# BGHESP32_Base_v1_1.net
KiCad netlist of a schematic drawn in EAGLE
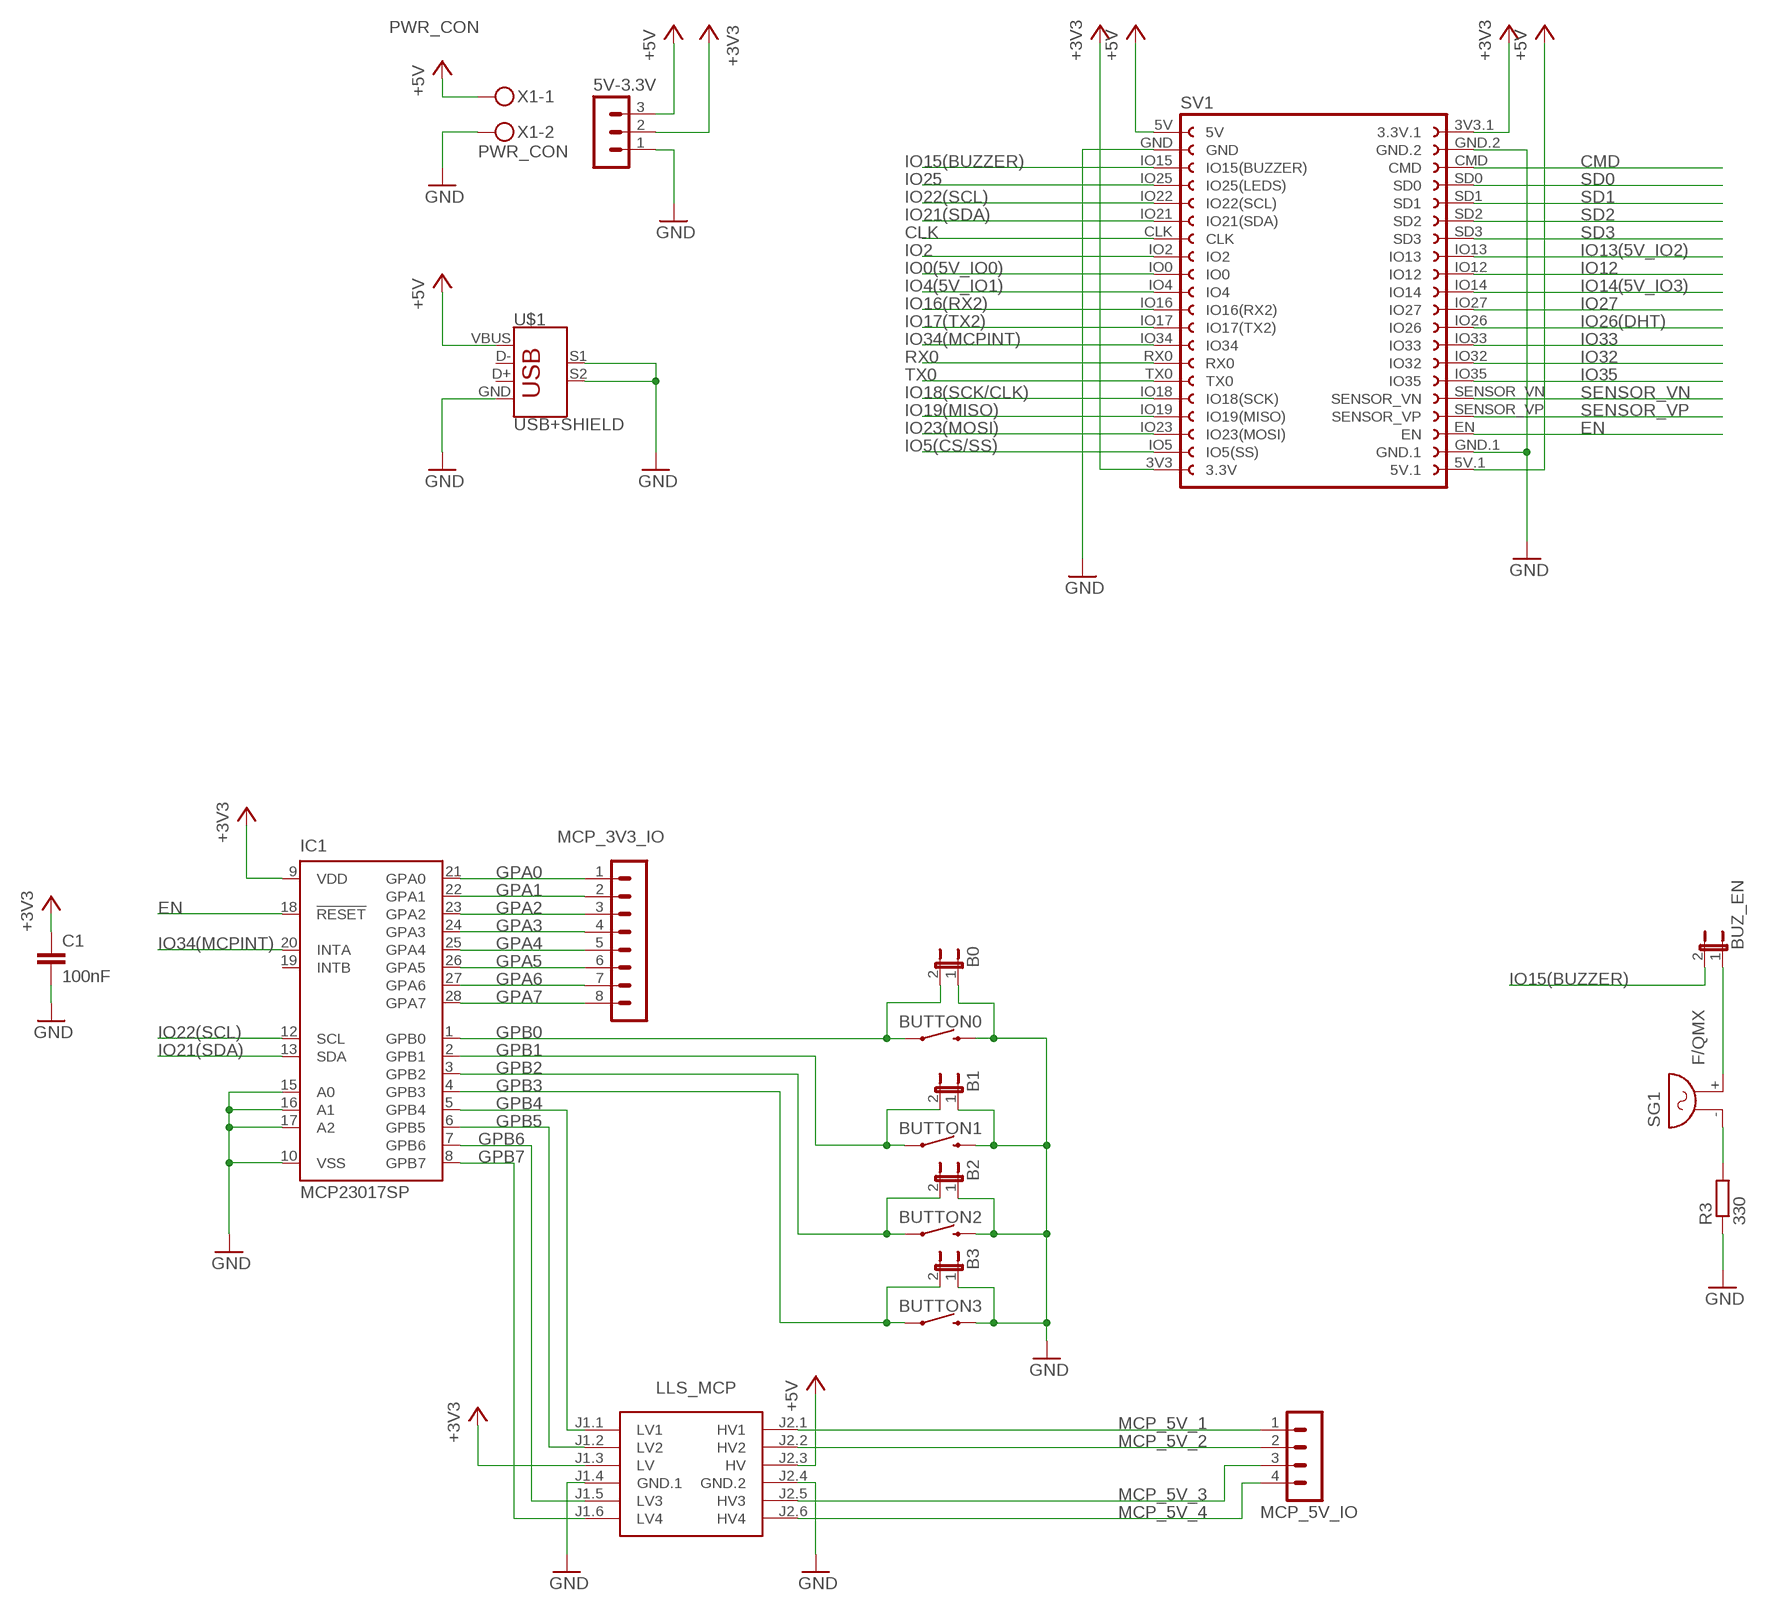
[diagram p0: schematic, sheet 1, part 1 of 2]
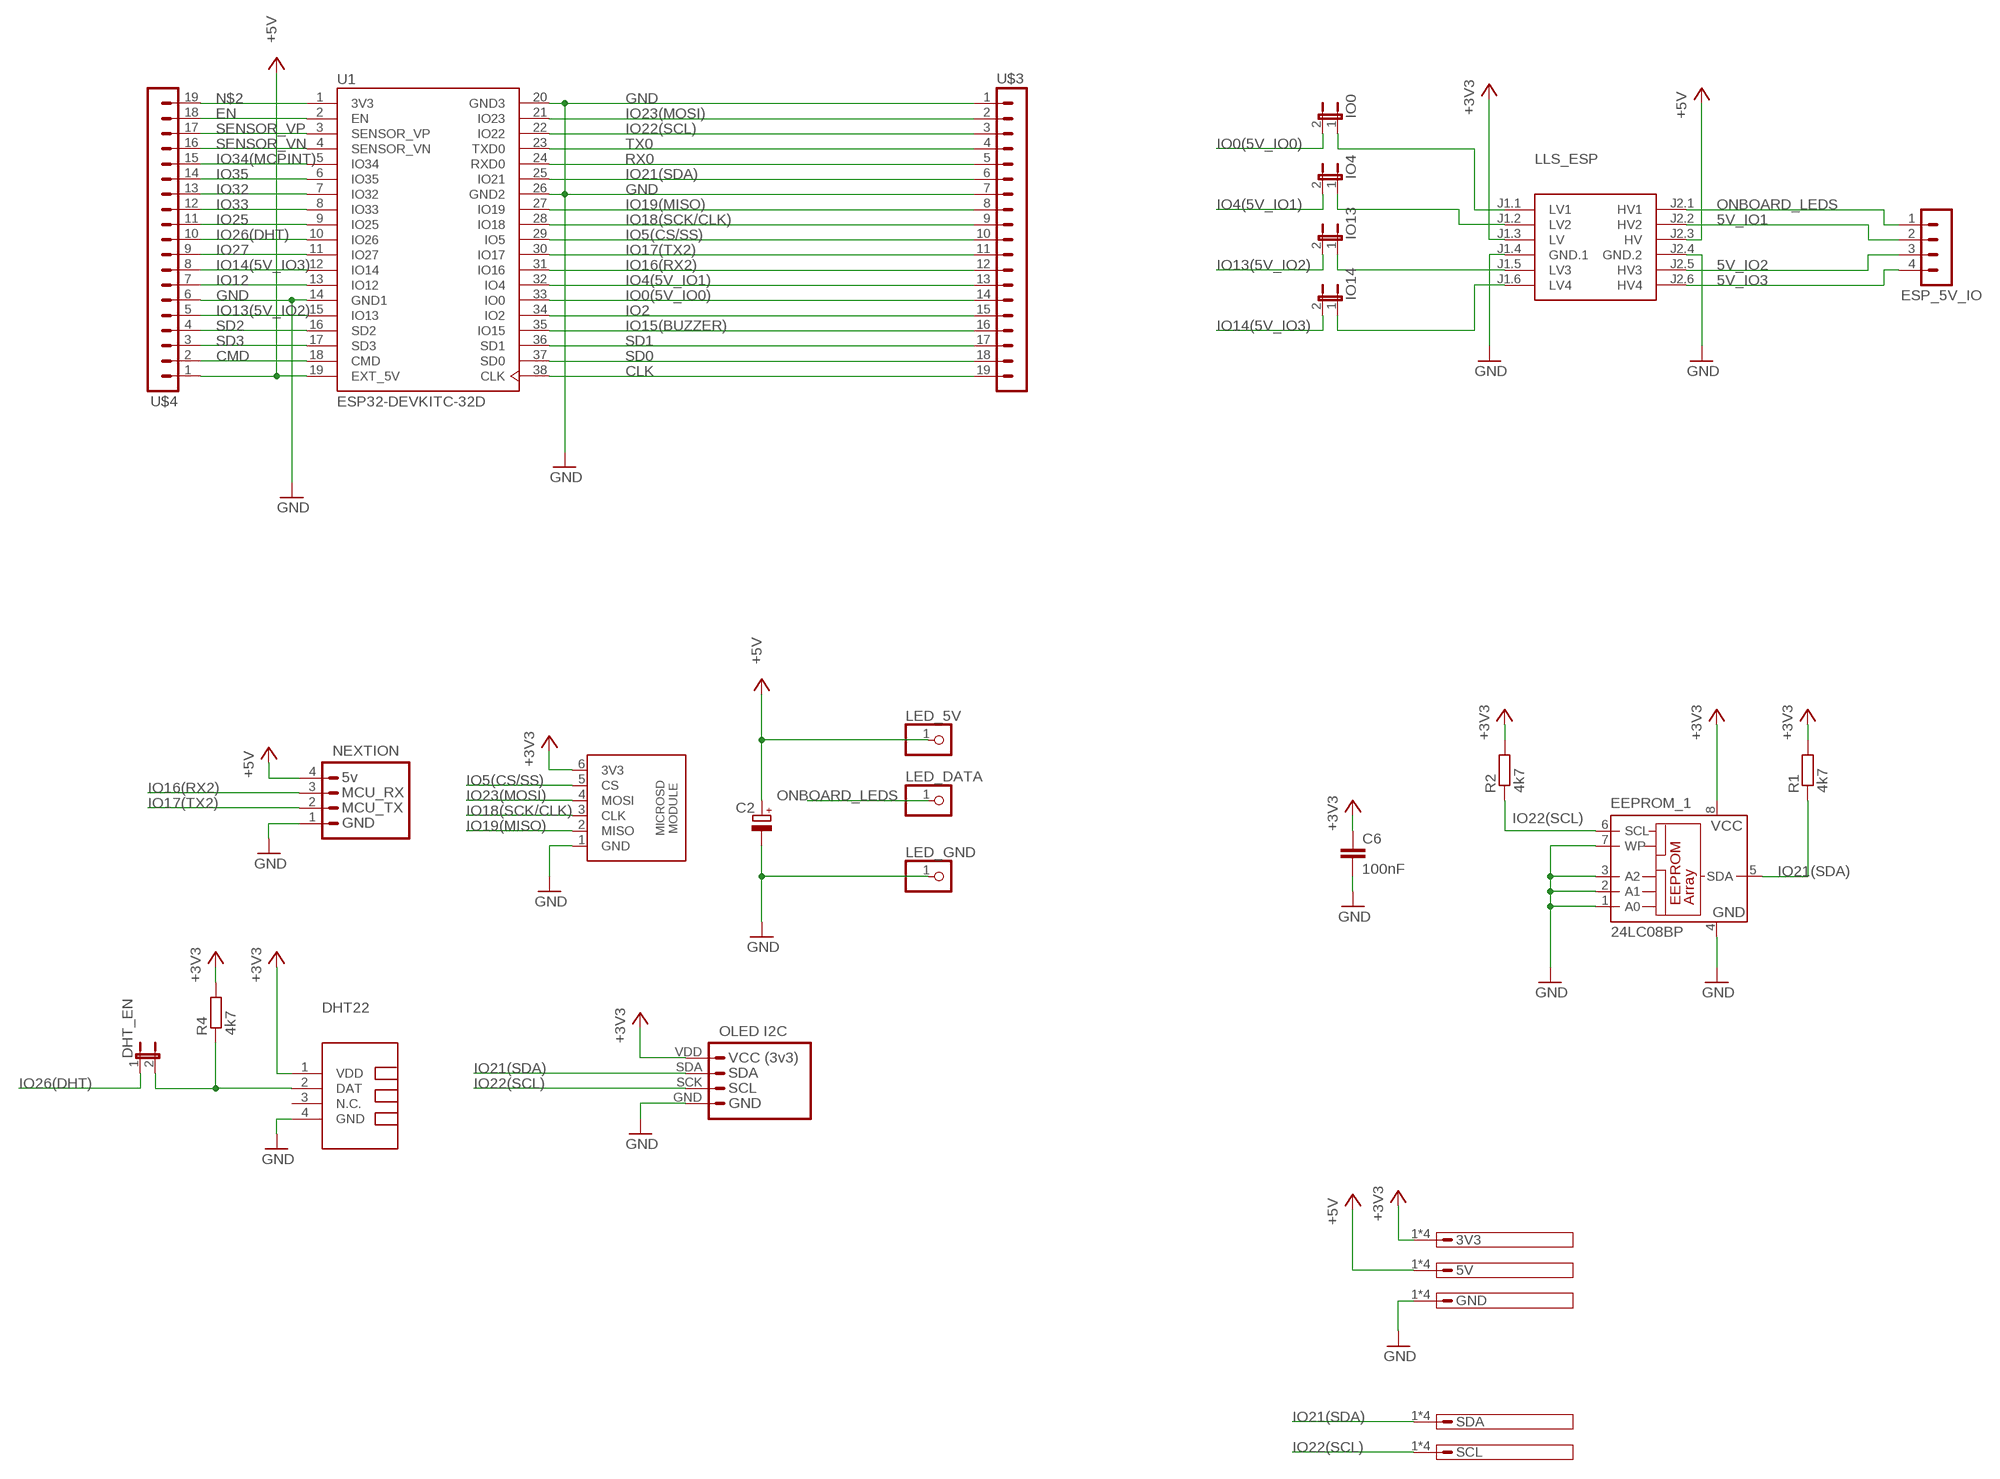
[diagram p1: schematic, sheet 1, part 2 of 2]

(export (version "E")
  (design (tool "Eeschema 10.0.6"))
  (components
    (comp (ref "3V3")
      (value "IO-OUT-4PIO-OUT-4[")
      (footprint "eagle-import:IO-OUT-4P")
      (libsource (lib "eagle-import") (part "IO-OUT-4PIO-OUT-4["))
    )
    (comp (ref "5V")
      (value "IO-OUT-4PIO-OUT-4[")
      (footprint "eagle-import:IO-OUT-4P")
      (libsource (lib "eagle-import") (part "IO-OUT-4PIO-OUT-4["))
    )
    (comp (ref "5V-3.3V")
      (value "MA03-1")
      (footprint "eagle-import:MA03-1")
      (libsource (lib "eagle-import") (part "MA03-1"))
    )
    (comp (ref "B0")
      (value "JP1E")
      (footprint "eagle-import:JP1")
      (libsource (lib "eagle-import") (part "JP1E"))
    )
    (comp (ref "B1")
      (value "JP1E")
      (footprint "eagle-import:JP1")
      (libsource (lib "eagle-import") (part "JP1E"))
    )
    (comp (ref "B2")
      (value "JP1E")
      (footprint "eagle-import:JP1")
      (libsource (lib "eagle-import") (part "JP1E"))
    )
    (comp (ref "B3")
      (value "JP1E")
      (footprint "eagle-import:JP1")
      (libsource (lib "eagle-import") (part "JP1E"))
    )
    (comp (ref "BUTTON0")
      (value "MOMENTARY-SWITCH-SPST-PTH-6.0MM")
      (footprint "eagle-import:TACTILE_SWITCH_PTH_6.0MM")
      (libsource (lib "eagle-import") (part "MOMENTARY-SWITCH-SPST-PTH-6.0MM"))
    )
    (comp (ref "BUTTON1")
      (value "MOMENTARY-SWITCH-SPST-PTH-6.0MM")
      (footprint "eagle-import:TACTILE_SWITCH_PTH_6.0MM")
      (libsource (lib "eagle-import") (part "MOMENTARY-SWITCH-SPST-PTH-6.0MM"))
    )
    (comp (ref "BUTTON2")
      (value "MOMENTARY-SWITCH-SPST-PTH-6.0MM")
      (footprint "eagle-import:TACTILE_SWITCH_PTH_6.0MM")
      (libsource (lib "eagle-import") (part "MOMENTARY-SWITCH-SPST-PTH-6.0MM"))
    )
    (comp (ref "BUTTON3")
      (value "MOMENTARY-SWITCH-SPST-PTH-6.0MM")
      (footprint "eagle-import:TACTILE_SWITCH_PTH_6.0MM")
      (libsource (lib "eagle-import") (part "MOMENTARY-SWITCH-SPST-PTH-6.0MM"))
    )
    (comp (ref "BUZ_EN")
      (value "JP1E")
      (footprint "eagle-import:JP1")
      (libsource (lib "eagle-import") (part "JP1E"))
    )
    (comp (ref "C1")
      (value "100nF")
      (footprint "eagle-import:C050-025X075")
      (libsource (lib "eagle-import") (part "C-EU050-025X075"))
    )
    (comp (ref "C2")
      (value "CPOL-EUE5-10.5")
      (footprint "eagle-import:E5-10,5")
      (libsource (lib "eagle-import") (part "CPOL-EUE5-10.5"))
    )
    (comp (ref "C6")
      (value "100nF")
      (footprint "eagle-import:C050-025X075")
      (libsource (lib "eagle-import") (part "C-EU050-025X075"))
    )
    (comp (ref "DHT22")
      (value "TEMP-HUM-SENSOR-DHT22")
      (footprint "eagle-import:TEMP-HUM-SENSOR-DHT22")
      (libsource (lib "eagle-import") (part "TEMP-HUM-SENSOR-DHT22"))
    )
    (comp (ref "DHT_EN")
      (value "JP1E")
      (footprint "eagle-import:JP1")
      (libsource (lib "eagle-import") (part "JP1E"))
    )
    (comp (ref "EEPROM_1")
      (value "24LC08BP")
      (footprint "eagle-import:DIL8")
      (fields (field (name "MF") "MICROCHIP") (field (name "MPN") "24LC08B/P"))
      (libsource (lib "eagle-import") (part "24PLC08B"))
    )
    (comp (ref "ESP_5V_IO")
      (value "MA04-1")
      (footprint "eagle-import:MA04-1")
      (libsource (lib "eagle-import") (part "MA04-1"))
    )
    (comp (ref "GND")
      (value "IO-OUT-4PIO-OUT-4[")
      (footprint "eagle-import:IO-OUT-4P")
      (libsource (lib "eagle-import") (part "IO-OUT-4PIO-OUT-4["))
    )
    (comp (ref "IC1")
      (value "MCP23017SP")
      (footprint "eagle-import:DIL28-3")
      (fields (field (name "MF") "MICROCHIP") (field (name "MPN") "MCP23017-E/SP"))
      (libsource (lib "eagle-import") (part "MCP23017SP"))
    )
    (comp (ref "IO0")
      (value "JP1E")
      (footprint "eagle-import:JP1")
      (libsource (lib "eagle-import") (part "JP1E"))
    )
    (comp (ref "IO4")
      (value "JP1E")
      (footprint "eagle-import:JP1")
      (libsource (lib "eagle-import") (part "JP1E"))
    )
    (comp (ref "IO13")
      (value "JP1E")
      (footprint "eagle-import:JP1")
      (libsource (lib "eagle-import") (part "JP1E"))
    )
    (comp (ref "IO14")
      (value "JP1E")
      (footprint "eagle-import:JP1")
      (libsource (lib "eagle-import") (part "JP1E"))
    )
    (comp (ref "LED_5V")
      (value "PINHD-1X1")
      (footprint "eagle-import:1X01")
      (libsource (lib "eagle-import") (part "PINHD-1X1"))
    )
    (comp (ref "LED_DATA")
      (value "PINHD-1X1")
      (footprint "eagle-import:1X01")
      (libsource (lib "eagle-import") (part "PINHD-1X1"))
    )
    (comp (ref "LED_GND")
      (value "PINHD-1X1")
      (footprint "eagle-import:1X01")
      (libsource (lib "eagle-import") (part "PINHD-1X1"))
    )
    (comp (ref "LLS_ESP")
      (value "LEVEL-SHIFTER-4CH")
      (footprint "eagle-import:LEVEL-SHIFTER-4CH")
      (libsource (lib "eagle-import") (part "LEVEL-SHIFTER-4CH"))
    )
    (comp (ref "LLS_MCP")
      (value "LEVEL-SHIFTER-4CH")
      (footprint "eagle-import:LEVEL-SHIFTER-4CH")
      (libsource (lib "eagle-import") (part "LEVEL-SHIFTER-4CH"))
    )
    (comp (ref "MCP_3V3_IO")
      (value "MA08-1")
      (footprint "eagle-import:MA08-1")
      (libsource (lib "eagle-import") (part "MA08-1"))
    )
    (comp (ref "MCP_5V_IO")
      (value "MA04-1")
      (footprint "eagle-import:MA04-1")
      (libsource (lib "eagle-import") (part "MA04-1"))
    )
    (comp (ref "R1")
      (value "4k7")
      (footprint "eagle-import:0207_10")
      (libsource (lib "eagle-import") (part "R-EU_0207/10"))
    )
    (comp (ref "R2")
      (value "4k7")
      (footprint "eagle-import:0207_10")
      (libsource (lib "eagle-import") (part "R-EU_0207/10"))
    )
    (comp (ref "R3")
      (value "330")
      (footprint "eagle-import:0207_10")
      (libsource (lib "eagle-import") (part "R-EU_0207/10"))
    )
    (comp (ref "R4")
      (value "4k7")
      (footprint "eagle-import:0207_10")
      (libsource (lib "eagle-import") (part "R-EU_0207/10"))
    )
    (comp (ref "SCL")
      (value "IO-OUT-4PIO-OUT-4[")
      (footprint "eagle-import:IO-OUT-4P")
      (libsource (lib "eagle-import") (part "IO-OUT-4PIO-OUT-4["))
    )
    (comp (ref "SDA")
      (value "IO-OUT-4PIO-OUT-4[")
      (footprint "eagle-import:IO-OUT-4P")
      (libsource (lib "eagle-import") (part "IO-OUT-4PIO-OUT-4["))
    )
    (comp (ref "SG1")
      (value "F/QMX")
      (footprint "eagle-import:F_QMX")
      (libsource (lib "eagle-import") (part "F/QMX"))
    )
    (comp (ref "SV1")
      (value "DAUGHTERBOARD_CON")
      (footprint "eagle-import:DAUGHTERBOARD_CON")
      (libsource (lib "eagle-import") (part "DAUGHTERBOARD_CON"))
    )
    (comp (ref "SV3")
      (value "NEXTION_CON")
      (footprint "eagle-import:NEXTION_CON")
      (libsource (lib "eagle-import") (part "NEXTION_CON"))
    )
    (comp (ref "U$1")
      (value "USB+SHIELD")
      (footprint "eagle-import:USB-B-PTH")
      (libsource (lib "eagle-import") (part "USB+SHIELD"))
    )
    (comp (ref "U$2")
      (value "I2C_OLED")
      (footprint "eagle-import:I2C_OLED")
      (libsource (lib "eagle-import") (part "I2C_OLED"))
    )
    (comp (ref "U$3")
      (value "MA19-1")
      (footprint "eagle-import:MA19-1")
      (libsource (lib "eagle-import") (part "MA19-1"))
    )
    (comp (ref "U$4")
      (value "MA19-1")
      (footprint "eagle-import:MA19-1")
      (libsource (lib "eagle-import") (part "MA19-1"))
    )
    (comp (ref "U$5")
      (value "SDCARD_MODULE")
      (footprint "eagle-import:SDCARD_MODULE")
      (libsource (lib "eagle-import") (part "SDCARD_MODULE"))
    )
    (comp (ref "U1")
      (value "ESP32-DEVKITC-32D")
      (footprint "eagle-import:MODULE_ESP32-DEVKITC-32D")
      (fields (field (name "MF") "Espressif Systems"))
      (libsource (lib "eagle-import") (part "ESP32-DEVKITC-32D"))
    )
    (comp (ref "X1")
      (value "PWR_CON")
      (footprint "eagle-import:MKDSN1,5_2-5,08")
      (libsource (lib "eagle-import") (part "MKDSN1,5/2-5,08"))
    )
  )
  (nets
    (net (code "1") (name "+3V3") (class "Default")
      (node (ref "3V3") (pin "1") (pinfunction "1_1") (pintype "passive"))
      (node (ref "3V3") (pin "2") (pinfunction "1_2") (pintype "passive"))
      (node (ref "3V3") (pin "3") (pinfunction "1_3") (pintype "passive"))
      (node (ref "3V3") (pin "4") (pinfunction "1_4") (pintype "passive"))
      (node (ref "5V-3.3V") (pin "2") (pinfunction "2_2") (pintype "passive"))
      (node (ref "C1") (pin "1") (pinfunction "1_1") (pintype "passive"))
      (node (ref "C6") (pin "1") (pinfunction "1_1") (pintype "passive"))
      (node (ref "DHT22") (pin "1") (pinfunction "VDD_1") (pintype "power_in"))
      (node (ref "EEPROM_1") (pin "8") (pinfunction "VCC_8") (pintype "power_in"))
      (node (ref "IC1") (pin "9") (pinfunction "VDD_9") (pintype "power_in"))
      (node (ref "LLS_ESP") (pin "J1.3") (pinfunction "LV_J1.3") (pintype "power_in"))
      (node (ref "LLS_MCP") (pin "J1.3") (pinfunction "LV_J1.3") (pintype "power_in"))
      (node (ref "R1") (pin "2") (pinfunction "2_2") (pintype "passive"))
      (node (ref "R2") (pin "2") (pinfunction "2_2") (pintype "passive"))
      (node (ref "R4") (pin "2") (pinfunction "2_2") (pintype "passive"))
      (node (ref "SV1") (pin "3V3") (pinfunction "3.3V_3V3") (pintype "passive"))
      (node (ref "SV1") (pin "3V3.1") (pinfunction "3.3V.1_3V3.1") (pintype "passive"))
      (node (ref "U$2") (pin "VDD") (pinfunction "VCC_VDD") (pintype "passive"))
      (node (ref "U$5") (pin "6") (pinfunction "3V3_6") (pintype "bidirectional"))
    )
    (net (code "2") (name "+5V") (class "Default")
      (node (ref "5V") (pin "1") (pinfunction "1_1") (pintype "passive"))
      (node (ref "5V") (pin "2") (pinfunction "1_2") (pintype "passive"))
      (node (ref "5V") (pin "3") (pinfunction "1_3") (pintype "passive"))
      (node (ref "5V") (pin "4") (pinfunction "1_4") (pintype "passive"))
      (node (ref "5V-3.3V") (pin "3") (pinfunction "3_3") (pintype "passive"))
      (node (ref "C2") (pin "+") (pinfunction "+_+") (pintype "passive"))
      (node (ref "LED_5V") (pin "1") (pinfunction "1_1") (pintype "passive"))
      (node (ref "LLS_ESP") (pin "J2.3") (pinfunction "HV_J2.3") (pintype "power_in"))
      (node (ref "LLS_MCP") (pin "J2.3") (pinfunction "HV_J2.3") (pintype "power_in"))
      (node (ref "SV1") (pin "5V") (pinfunction "5V_5V") (pintype "passive"))
      (node (ref "SV1") (pin "5V.1") (pinfunction "5V.1_5V.1") (pintype "passive"))
      (node (ref "SV3") (pin "4") (pinfunction "4_4") (pintype "passive"))
      (node (ref "U$1") (pin "VBUS") (pinfunction "VBUS_VBUS") (pintype "power_in"))
      (node (ref "U$4") (pin "1") (pinfunction "1_1") (pintype "passive"))
      (node (ref "U1") (pin "19") (pinfunction "EXT_5V_19") (pintype "power_in"))
      (node (ref "X1") (pin "1") (pinfunction "KL_1") (pintype "passive"))
    )
    (net (code "3") (name "/5V_IO1") (class "Default")
      (node (ref "ESP_5V_IO") (pin "2") (pinfunction "2_2") (pintype "passive"))
      (node (ref "LLS_ESP") (pin "J2.2") (pinfunction "HV2_J2.2") (pintype "bidirectional"))
    )
    (net (code "4") (name "/5V_IO2") (class "Default")
      (node (ref "ESP_5V_IO") (pin "3") (pinfunction "3_3") (pintype "passive"))
      (node (ref "LLS_ESP") (pin "J2.5") (pinfunction "HV3_J2.5") (pintype "bidirectional"))
    )
    (net (code "5") (name "/5V_IO3") (class "Default")
      (node (ref "ESP_5V_IO") (pin "4") (pinfunction "4_4") (pintype "passive"))
      (node (ref "LLS_ESP") (pin "J2.6") (pinfunction "HV4_J2.6") (pintype "bidirectional"))
    )
    (net (code "6") (name "/CLK") (class "Default")
      (node (ref "SV1") (pin "CLK") (pinfunction "CLK_CLK") (pintype "passive"))
      (node (ref "U$3") (pin "19") (pinfunction "19_19") (pintype "passive"))
      (node (ref "U1") (pin "38") (pinfunction "CLK_38") (pintype "input"))
    )
    (net (code "7") (name "/CMD") (class "Default")
      (node (ref "SV1") (pin "CMD") (pinfunction "CMD_CMD") (pintype "passive"))
      (node (ref "U$4") (pin "2") (pinfunction "2_2") (pintype "passive"))
      (node (ref "U1") (pin "18") (pinfunction "CMD_18") (pintype "bidirectional"))
    )
    (net (code "8") (name "/EN") (class "Default")
      (node (ref "IC1") (pin "18") (pinfunction "~{RESET}_18") (pintype "input"))
      (node (ref "SV1") (pin "EN") (pinfunction "EN_EN") (pintype "passive"))
      (node (ref "U$4") (pin "18") (pinfunction "18_18") (pintype "passive"))
      (node (ref "U1") (pin "2") (pinfunction "EN_2") (pintype "input"))
    )
    (net (code "9") (name "/GPA0") (class "Default")
      (node (ref "IC1") (pin "21") (pinfunction "GPA0_21") (pintype "bidirectional"))
      (node (ref "MCP_3V3_IO") (pin "1") (pinfunction "1_1") (pintype "passive"))
    )
    (net (code "10") (name "/GPA1") (class "Default")
      (node (ref "IC1") (pin "22") (pinfunction "GPA1_22") (pintype "bidirectional"))
      (node (ref "MCP_3V3_IO") (pin "2") (pinfunction "2_2") (pintype "passive"))
    )
    (net (code "11") (name "/GPA2") (class "Default")
      (node (ref "IC1") (pin "23") (pinfunction "GPA2_23") (pintype "bidirectional"))
      (node (ref "MCP_3V3_IO") (pin "3") (pinfunction "3_3") (pintype "passive"))
    )
    (net (code "12") (name "/GPA3") (class "Default")
      (node (ref "IC1") (pin "24") (pinfunction "GPA3_24") (pintype "bidirectional"))
      (node (ref "MCP_3V3_IO") (pin "4") (pinfunction "4_4") (pintype "passive"))
    )
    (net (code "13") (name "/GPA4") (class "Default")
      (node (ref "IC1") (pin "25") (pinfunction "GPA4_25") (pintype "bidirectional"))
      (node (ref "MCP_3V3_IO") (pin "5") (pinfunction "5_5") (pintype "passive"))
    )
    (net (code "14") (name "/GPA5") (class "Default")
      (node (ref "IC1") (pin "26") (pinfunction "GPA5_26") (pintype "bidirectional"))
      (node (ref "MCP_3V3_IO") (pin "6") (pinfunction "6_6") (pintype "passive"))
    )
    (net (code "15") (name "/GPA6") (class "Default")
      (node (ref "IC1") (pin "27") (pinfunction "GPA6_27") (pintype "bidirectional"))
      (node (ref "MCP_3V3_IO") (pin "7") (pinfunction "7_7") (pintype "passive"))
    )
    (net (code "16") (name "/GPA7") (class "Default")
      (node (ref "IC1") (pin "28") (pinfunction "GPA7_28") (pintype "bidirectional"))
      (node (ref "MCP_3V3_IO") (pin "8") (pinfunction "8_8") (pintype "passive"))
    )
    (net (code "17") (name "/GPB0") (class "Default")
      (node (ref "B0") (pin "2") (pinfunction "2_2") (pintype "passive"))
      (node (ref "BUTTON0") (pin "1") (pinfunction "1_1") (pintype "passive"))
      (node (ref "IC1") (pin "1") (pinfunction "GPB0_1") (pintype "bidirectional"))
    )
    (net (code "18") (name "/GPB1") (class "Default")
      (node (ref "B1") (pin "2") (pinfunction "2_2") (pintype "passive"))
      (node (ref "BUTTON1") (pin "1") (pinfunction "1_1") (pintype "passive"))
      (node (ref "IC1") (pin "2") (pinfunction "GPB1_2") (pintype "bidirectional"))
    )
    (net (code "19") (name "/GPB2") (class "Default")
      (node (ref "B2") (pin "2") (pinfunction "2_2") (pintype "passive"))
      (node (ref "BUTTON2") (pin "1") (pinfunction "1_1") (pintype "passive"))
      (node (ref "IC1") (pin "3") (pinfunction "GPB2_3") (pintype "bidirectional"))
    )
    (net (code "20") (name "/GPB3") (class "Default")
      (node (ref "B3") (pin "2") (pinfunction "2_2") (pintype "passive"))
      (node (ref "BUTTON3") (pin "1") (pinfunction "1_1") (pintype "passive"))
      (node (ref "IC1") (pin "4") (pinfunction "GPB3_4") (pintype "bidirectional"))
    )
    (net (code "21") (name "/GPB4") (class "Default")
      (node (ref "IC1") (pin "5") (pinfunction "GPB4_5") (pintype "bidirectional"))
      (node (ref "LLS_MCP") (pin "J1.1") (pinfunction "LV1_J1.1") (pintype "bidirectional"))
    )
    (net (code "22") (name "/GPB5") (class "Default")
      (node (ref "IC1") (pin "6") (pinfunction "GPB5_6") (pintype "bidirectional"))
      (node (ref "LLS_MCP") (pin "J1.2") (pinfunction "LV2_J1.2") (pintype "bidirectional"))
    )
    (net (code "23") (name "/GPB6") (class "Default")
      (node (ref "IC1") (pin "7") (pinfunction "GPB6_7") (pintype "bidirectional"))
      (node (ref "LLS_MCP") (pin "J1.5") (pinfunction "LV3_J1.5") (pintype "bidirectional"))
    )
    (net (code "24") (name "/GPB7") (class "Default")
      (node (ref "IC1") (pin "8") (pinfunction "GPB7_8") (pintype "bidirectional"))
      (node (ref "LLS_MCP") (pin "J1.6") (pinfunction "LV4_J1.6") (pintype "bidirectional"))
    )
    (net (code "25") (name "/IO0(5V_IO0)") (class "Default")
      (node (ref "IO0") (pin "2") (pinfunction "2_2") (pintype "passive"))
      (node (ref "SV1") (pin "IO0") (pinfunction "IO0_IO0") (pintype "passive"))
      (node (ref "U$3") (pin "14") (pinfunction "14_14") (pintype "passive"))
      (node (ref "U1") (pin "33") (pinfunction "IO0_33") (pintype "bidirectional"))
    )
    (net (code "26") (name "/IO2") (class "Default")
      (node (ref "SV1") (pin "IO2") (pinfunction "IO2_IO2") (pintype "passive"))
      (node (ref "U$3") (pin "15") (pinfunction "15_15") (pintype "passive"))
      (node (ref "U1") (pin "34") (pinfunction "IO2_34") (pintype "bidirectional"))
    )
    (net (code "27") (name "/IO4(5V_IO1)") (class "Default")
      (node (ref "IO4") (pin "2") (pinfunction "2_2") (pintype "passive"))
      (node (ref "SV1") (pin "IO4") (pinfunction "IO4_IO4") (pintype "passive"))
      (node (ref "U$3") (pin "13") (pinfunction "13_13") (pintype "passive"))
      (node (ref "U1") (pin "32") (pinfunction "IO4_32") (pintype "bidirectional"))
    )
    (net (code "28") (name "/IO5(CS{slash}SS)") (class "Default")
      (node (ref "SV1") (pin "IO5") (pinfunction "IO5(SS)_IO5") (pintype "passive"))
      (node (ref "U$3") (pin "10") (pinfunction "10_10") (pintype "passive"))
      (node (ref "U$5") (pin "5") (pinfunction "CS_5") (pintype "bidirectional"))
      (node (ref "U1") (pin "29") (pinfunction "IO5_29") (pintype "bidirectional"))
    )
    (net (code "29") (name "/IO12") (class "Default")
      (node (ref "SV1") (pin "IO12") (pinfunction "IO12_IO12") (pintype "passive"))
      (node (ref "U$4") (pin "7") (pinfunction "7_7") (pintype "passive"))
      (node (ref "U1") (pin "13") (pinfunction "IO12_13") (pintype "bidirectional"))
    )
    (net (code "30") (name "/IO13(5V_IO2)") (class "Default")
      (node (ref "IO13") (pin "2") (pinfunction "2_2") (pintype "passive"))
      (node (ref "SV1") (pin "IO13") (pinfunction "IO13_IO13") (pintype "passive"))
      (node (ref "U$4") (pin "5") (pinfunction "5_5") (pintype "passive"))
      (node (ref "U1") (pin "15") (pinfunction "IO13_15") (pintype "bidirectional"))
    )
    (net (code "31") (name "/IO14(5V_IO3)") (class "Default")
      (node (ref "IO14") (pin "2") (pinfunction "2_2") (pintype "passive"))
      (node (ref "SV1") (pin "IO14") (pinfunction "IO14_IO14") (pintype "passive"))
      (node (ref "U$4") (pin "8") (pinfunction "8_8") (pintype "passive"))
      (node (ref "U1") (pin "12") (pinfunction "IO14_12") (pintype "bidirectional"))
    )
    (net (code "32") (name "/IO15(BUZZER)") (class "Default")
      (node (ref "BUZ_EN") (pin "2") (pinfunction "2_2") (pintype "passive"))
      (node (ref "SV1") (pin "IO15") (pinfunction "IO15(BUZZER)_IO15") (pintype "passive"))
      (node (ref "U$3") (pin "16") (pinfunction "16_16") (pintype "passive"))
      (node (ref "U1") (pin "35") (pinfunction "IO15_35") (pintype "bidirectional"))
    )
    (net (code "33") (name "/IO16(RX2)") (class "Default")
      (node (ref "SV1") (pin "IO16") (pinfunction "IO16(RX2)_IO16") (pintype "passive"))
      (node (ref "SV3") (pin "3") (pinfunction "3_3") (pintype "passive"))
      (node (ref "U$3") (pin "12") (pinfunction "12_12") (pintype "passive"))
      (node (ref "U1") (pin "31") (pinfunction "IO16_31") (pintype "bidirectional"))
    )
    (net (code "34") (name "/IO17(TX2)") (class "Default")
      (node (ref "SV1") (pin "IO17") (pinfunction "IO17(TX2)_IO17") (pintype "passive"))
      (node (ref "SV3") (pin "2") (pinfunction "2_2") (pintype "passive"))
      (node (ref "U$3") (pin "11") (pinfunction "11_11") (pintype "passive"))
      (node (ref "U1") (pin "30") (pinfunction "IO17_30") (pintype "bidirectional"))
    )
    (net (code "35") (name "/IO18(SCK{slash}CLK)") (class "Default")
      (node (ref "SV1") (pin "IO18") (pinfunction "IO18(SCK)_IO18") (pintype "passive"))
      (node (ref "U$3") (pin "9") (pinfunction "9_9") (pintype "passive"))
      (node (ref "U$5") (pin "3") (pinfunction "CLK_3") (pintype "bidirectional"))
      (node (ref "U1") (pin "28") (pinfunction "IO18_28") (pintype "bidirectional"))
    )
    (net (code "36") (name "/IO19(MISO)") (class "Default")
      (node (ref "SV1") (pin "IO19") (pinfunction "IO19(MISO)_IO19") (pintype "passive"))
      (node (ref "U$3") (pin "8") (pinfunction "8_8") (pintype "passive"))
      (node (ref "U$5") (pin "2") (pinfunction "MISO_2") (pintype "bidirectional"))
      (node (ref "U1") (pin "27") (pinfunction "IO19_27") (pintype "bidirectional"))
    )
    (net (code "37") (name "/IO21(SDA)") (class "Default")
      (node (ref "EEPROM_1") (pin "5") (pinfunction "SDA_5") (pintype "bidirectional"))
      (node (ref "IC1") (pin "13") (pinfunction "SDA_13") (pintype "bidirectional"))
      (node (ref "R1") (pin "1") (pinfunction "1_1") (pintype "passive"))
      (node (ref "SDA") (pin "1") (pinfunction "1_1") (pintype "passive"))
      (node (ref "SDA") (pin "2") (pinfunction "1_2") (pintype "passive"))
      (node (ref "SDA") (pin "3") (pinfunction "1_3") (pintype "passive"))
      (node (ref "SDA") (pin "4") (pinfunction "1_4") (pintype "passive"))
      (node (ref "SV1") (pin "IO21") (pinfunction "IO21(SDA)_IO21") (pintype "passive"))
      (node (ref "U$2") (pin "SDA") (pinfunction "SDA_SDA") (pintype "passive"))
      (node (ref "U$3") (pin "6") (pinfunction "6_6") (pintype "passive"))
      (node (ref "U1") (pin "25") (pinfunction "IO21_25") (pintype "bidirectional"))
    )
    (net (code "38") (name "/IO22(SCL)") (class "Default")
      (node (ref "EEPROM_1") (pin "6") (pinfunction "SCL_6") (pintype "input"))
      (node (ref "IC1") (pin "12") (pinfunction "SCL_12") (pintype "input"))
      (node (ref "R2") (pin "1") (pinfunction "1_1") (pintype "passive"))
      (node (ref "SCL") (pin "1") (pinfunction "1_1") (pintype "passive"))
      (node (ref "SCL") (pin "2") (pinfunction "1_2") (pintype "passive"))
      (node (ref "SCL") (pin "3") (pinfunction "1_3") (pintype "passive"))
      (node (ref "SCL") (pin "4") (pinfunction "1_4") (pintype "passive"))
      (node (ref "SV1") (pin "IO22") (pinfunction "IO22(SCL)_IO22") (pintype "passive"))
      (node (ref "U$2") (pin "SCK") (pinfunction "SCL_SCK") (pintype "passive"))
      (node (ref "U$3") (pin "3") (pinfunction "3_3") (pintype "passive"))
      (node (ref "U1") (pin "22") (pinfunction "IO22_22") (pintype "bidirectional"))
    )
    (net (code "39") (name "/IO23(MOSI)") (class "Default")
      (node (ref "SV1") (pin "IO23") (pinfunction "IO23(MOSI)_IO23") (pintype "passive"))
      (node (ref "U$3") (pin "2") (pinfunction "2_2") (pintype "passive"))
      (node (ref "U$5") (pin "4") (pinfunction "MOSI_4") (pintype "bidirectional"))
      (node (ref "U1") (pin "21") (pinfunction "IO23_21") (pintype "bidirectional"))
    )
    (net (code "40") (name "/IO25") (class "Default")
      (node (ref "SV1") (pin "IO25") (pinfunction "IO25(LEDS)_IO25") (pintype "passive"))
      (node (ref "U$4") (pin "11") (pinfunction "11_11") (pintype "passive"))
      (node (ref "U1") (pin "9") (pinfunction "IO25_9") (pintype "bidirectional"))
    )
    (net (code "41") (name "/IO26(DHT)") (class "Default")
      (node (ref "DHT_EN") (pin "1") (pinfunction "1_1") (pintype "passive"))
      (node (ref "SV1") (pin "IO26") (pinfunction "IO26_IO26") (pintype "passive"))
      (node (ref "U$4") (pin "10") (pinfunction "10_10") (pintype "passive"))
      (node (ref "U1") (pin "10") (pinfunction "IO26_10") (pintype "bidirectional"))
    )
    (net (code "42") (name "/IO27") (class "Default")
      (node (ref "SV1") (pin "IO27") (pinfunction "IO27_IO27") (pintype "passive"))
      (node (ref "U$4") (pin "9") (pinfunction "9_9") (pintype "passive"))
      (node (ref "U1") (pin "11") (pinfunction "IO27_11") (pintype "bidirectional"))
    )
    (net (code "43") (name "/IO32") (class "Default")
      (node (ref "SV1") (pin "IO32") (pinfunction "IO32_IO32") (pintype "passive"))
      (node (ref "U$4") (pin "13") (pinfunction "13_13") (pintype "passive"))
      (node (ref "U1") (pin "7") (pinfunction "IO32_7") (pintype "bidirectional"))
    )
    (net (code "44") (name "/IO33") (class "Default")
      (node (ref "SV1") (pin "IO33") (pinfunction "IO33_IO33") (pintype "passive"))
      (node (ref "U$4") (pin "12") (pinfunction "12_12") (pintype "passive"))
      (node (ref "U1") (pin "8") (pinfunction "IO33_8") (pintype "bidirectional"))
    )
    (net (code "45") (name "/IO34(MCPINT)") (class "Default")
      (node (ref "IC1") (pin "20") (pinfunction "INTA_20") (pintype "output"))
      (node (ref "SV1") (pin "IO34") (pinfunction "IO34_IO34") (pintype "passive"))
      (node (ref "U$4") (pin "15") (pinfunction "15_15") (pintype "passive"))
      (node (ref "U1") (pin "5") (pinfunction "IO34_5") (pintype "bidirectional"))
    )
    (net (code "46") (name "/IO35") (class "Default")
      (node (ref "SV1") (pin "IO35") (pinfunction "IO35_IO35") (pintype "passive"))
      (node (ref "U$4") (pin "14") (pinfunction "14_14") (pintype "passive"))
      (node (ref "U1") (pin "6") (pinfunction "IO35_6") (pintype "bidirectional"))
    )
    (net (code "47") (name "/MCP_5V_1") (class "Default")
      (node (ref "LLS_MCP") (pin "J2.1") (pinfunction "HV1_J2.1") (pintype "bidirectional"))
      (node (ref "MCP_5V_IO") (pin "1") (pinfunction "1_1") (pintype "passive"))
    )
    (net (code "48") (name "/MCP_5V_2") (class "Default")
      (node (ref "LLS_MCP") (pin "J2.2") (pinfunction "HV2_J2.2") (pintype "bidirectional"))
      (node (ref "MCP_5V_IO") (pin "2") (pinfunction "2_2") (pintype "passive"))
    )
    (net (code "49") (name "/MCP_5V_3") (class "Default")
      (node (ref "LLS_MCP") (pin "J2.5") (pinfunction "HV3_J2.5") (pintype "bidirectional"))
      (node (ref "MCP_5V_IO") (pin "3") (pinfunction "3_3") (pintype "passive"))
    )
    (net (code "50") (name "/MCP_5V_4") (class "Default")
      (node (ref "LLS_MCP") (pin "J2.6") (pinfunction "HV4_J2.6") (pintype "bidirectional"))
      (node (ref "MCP_5V_IO") (pin "4") (pinfunction "4_4") (pintype "passive"))
    )
    (net (code "51") (name "/N$2") (class "Default")
      (node (ref "U$4") (pin "19") (pinfunction "19_19") (pintype "passive"))
      (node (ref "U1") (pin "1") (pinfunction "3V3_1") (pintype "power_in"))
    )
    (net (code "52") (name "/ONBOARD_LEDS") (class "Default")
      (node (ref "ESP_5V_IO") (pin "1") (pinfunction "1_1") (pintype "passive"))
      (node (ref "LED_DATA") (pin "1") (pinfunction "1_1") (pintype "passive"))
      (node (ref "LLS_ESP") (pin "J2.1") (pinfunction "HV1_J2.1") (pintype "bidirectional"))
    )
    (net (code "53") (name "/RX0") (class "Default")
      (node (ref "SV1") (pin "RX0") (pinfunction "RX0_RX0") (pintype "passive"))
      (node (ref "U$3") (pin "5") (pinfunction "5_5") (pintype "passive"))
      (node (ref "U1") (pin "24") (pinfunction "RXD0_24") (pintype "input"))
    )
    (net (code "54") (name "/SD0") (class "Default")
      (node (ref "SV1") (pin "SD0") (pinfunction "SD0_SD0") (pintype "passive"))
      (node (ref "U$3") (pin "18") (pinfunction "18_18") (pintype "passive"))
      (node (ref "U1") (pin "37") (pinfunction "SD0_37") (pintype "bidirectional"))
    )
    (net (code "55") (name "/SD1") (class "Default")
      (node (ref "SV1") (pin "SD1") (pinfunction "SD1_SD1") (pintype "passive"))
      (node (ref "U$3") (pin "17") (pinfunction "17_17") (pintype "passive"))
      (node (ref "U1") (pin "36") (pinfunction "SD1_36") (pintype "bidirectional"))
    )
    (net (code "56") (name "/SD2") (class "Default")
      (node (ref "SV1") (pin "SD2") (pinfunction "SD2_SD2") (pintype "passive"))
      (node (ref "U$4") (pin "4") (pinfunction "4_4") (pintype "passive"))
      (node (ref "U1") (pin "16") (pinfunction "SD2_16") (pintype "bidirectional"))
    )
    (net (code "57") (name "/SD3") (class "Default")
      (node (ref "SV1") (pin "SD3") (pinfunction "SD3_SD3") (pintype "passive"))
      (node (ref "U$4") (pin "3") (pinfunction "3_3") (pintype "passive"))
      (node (ref "U1") (pin "17") (pinfunction "SD3_17") (pintype "bidirectional"))
    )
    (net (code "58") (name "/SENSOR_VN") (class "Default")
      (node (ref "SV1") (pin "SENSOR_VN") (pinfunction "SENSOR_VN_SENSOR_VN") (pintype "passive"))
      (node (ref "U$4") (pin "16") (pinfunction "16_16") (pintype "passive"))
      (node (ref "U1") (pin "4") (pinfunction "SENSOR_VN_4") (pintype "input"))
    )
    (net (code "59") (name "/SENSOR_VP") (class "Default")
      (node (ref "SV1") (pin "SENSOR_VP") (pinfunction "SENSOR_VP_SENSOR_VP") (pintype "passive"))
      (node (ref "U$4") (pin "17") (pinfunction "17_17") (pintype "passive"))
      (node (ref "U1") (pin "3") (pinfunction "SENSOR_VP_3") (pintype "input"))
    )
    (net (code "60") (name "/TX0") (class "Default")
      (node (ref "SV1") (pin "TX0") (pinfunction "TX0_TX0") (pintype "passive"))
      (node (ref "U$3") (pin "4") (pinfunction "4_4") (pintype "passive"))
      (node (ref "U1") (pin "23") (pinfunction "TXD0_23") (pintype "output"))
    )
    (net (code "61") (name "GND") (class "Default")
      (node (ref "5V-3.3V") (pin "1") (pinfunction "1_1") (pintype "passive"))
      (node (ref "B0") (pin "1") (pinfunction "1_1") (pintype "passive"))
      (node (ref "B1") (pin "1") (pinfunction "1_1") (pintype "passive"))
      (node (ref "B2") (pin "1") (pinfunction "1_1") (pintype "passive"))
      (node (ref "B3") (pin "1") (pinfunction "1_1") (pintype "passive"))
      (node (ref "BUTTON0") (pin "3") (pinfunction "2_3") (pintype "passive"))
      (node (ref "BUTTON1") (pin "3") (pinfunction "2_3") (pintype "passive"))
      (node (ref "BUTTON2") (pin "3") (pinfunction "2_3") (pintype "passive"))
      (node (ref "BUTTON3") (pin "3") (pinfunction "2_3") (pintype "passive"))
      (node (ref "C1") (pin "2") (pinfunction "2_2") (pintype "passive"))
      (node (ref "C2") (pin "-") (pinfunction "-_-") (pintype "passive"))
      (node (ref "C6") (pin "2") (pinfunction "2_2") (pintype "passive"))
      (node (ref "DHT22") (pin "4") (pinfunction "GND_4") (pintype "power_in"))
      (node (ref "EEPROM_1") (pin "1") (pinfunction "A0_1") (pintype "input"))
      (node (ref "EEPROM_1") (pin "2") (pinfunction "A1_2") (pintype "input"))
      (node (ref "EEPROM_1") (pin "3") (pinfunction "A2_3") (pintype "input"))
      (node (ref "EEPROM_1") (pin "4") (pinfunction "GND_4") (pintype "power_in"))
      (node (ref "EEPROM_1") (pin "7") (pinfunction "WP_7") (pintype "input"))
      (node (ref "GND") (pin "1") (pinfunction "1_1") (pintype "passive"))
      (node (ref "GND") (pin "2") (pinfunction "1_2") (pintype "passive"))
      (node (ref "GND") (pin "3") (pinfunction "1_3") (pintype "passive"))
      (node (ref "GND") (pin "4") (pinfunction "1_4") (pintype "passive"))
      (node (ref "IC1") (pin "10") (pinfunction "VSS_10") (pintype "power_in"))
      (node (ref "IC1") (pin "15") (pinfunction "A0_15") (pintype "input"))
      (node (ref "IC1") (pin "16") (pinfunction "A1_16") (pintype "input"))
      (node (ref "IC1") (pin "17") (pinfunction "A2_17") (pintype "input"))
      (node (ref "LED_GND") (pin "1") (pinfunction "1_1") (pintype "passive"))
      (node (ref "LLS_ESP") (pin "J1.4") (pinfunction "GND.1_J1.4") (pintype "power_in"))
      (node (ref "LLS_ESP") (pin "J2.4") (pinfunction "GND.2_J2.4") (pintype "power_in"))
      (node (ref "LLS_MCP") (pin "J1.4") (pinfunction "GND.1_J1.4") (pintype "power_in"))
      (node (ref "LLS_MCP") (pin "J2.4") (pinfunction "GND.2_J2.4") (pintype "power_in"))
      (node (ref "R3") (pin "1") (pinfunction "1_1") (pintype "passive"))
      (node (ref "SV1") (pin "GND") (pinfunction "GND_GND") (pintype "passive"))
      (node (ref "SV1") (pin "GND.1") (pinfunction "GND.1_GND.1") (pintype "passive"))
      (node (ref "SV1") (pin "GND.2") (pinfunction "GND.2_GND.2") (pintype "passive"))
      (node (ref "SV3") (pin "1") (pinfunction "1_1") (pintype "passive"))
      (node (ref "U$1") (pin "GND") (pinfunction "GND_GND") (pintype "power_in"))
      (node (ref "U$1") (pin "S1") (pinfunction "S1_S1") (pintype "bidirectional"))
      (node (ref "U$1") (pin "S2") (pinfunction "S2_S2") (pintype "bidirectional"))
      (node (ref "U$2") (pin "GND") (pinfunction "GND_GND") (pintype "passive"))
      (node (ref "U$3") (pin "1") (pinfunction "1_1") (pintype "passive"))
      (node (ref "U$3") (pin "7") (pinfunction "7_7") (pintype "passive"))
      (node (ref "U$4") (pin "6") (pinfunction "6_6") (pintype "passive"))
      (node (ref "U$5") (pin "1") (pinfunction "GND_1") (pintype "bidirectional"))
      (node (ref "U1") (pin "14") (pinfunction "GND1_14") (pintype "power_in"))
      (node (ref "U1") (pin "20") (pinfunction "GND3_20") (pintype "power_in"))
      (node (ref "U1") (pin "26") (pinfunction "GND2_26") (pintype "power_in"))
      (node (ref "X1") (pin "2") (pinfunction "KL_2") (pintype "passive"))
    )
    (net (code "62") (name "Net-(DHT22-DAT)") (class "Default")
      (node (ref "DHT22") (pin "2") (pinfunction "DAT_2") (pintype "bidirectional"))
      (node (ref "DHT_EN") (pin "2") (pinfunction "2_2") (pintype "passive"))
      (node (ref "R4") (pin "1") (pinfunction "1_1") (pintype "passive"))
    )
    (net (code "63") (name "Net-(LLS_ESP-LV1)") (class "Default")
      (node (ref "IO0") (pin "1") (pinfunction "1_1") (pintype "passive"))
      (node (ref "LLS_ESP") (pin "J1.1") (pinfunction "LV1_J1.1") (pintype "bidirectional"))
    )
    (net (code "64") (name "Net-(LLS_ESP-LV2)") (class "Default")
      (node (ref "IO4") (pin "1") (pinfunction "1_1") (pintype "passive"))
      (node (ref "LLS_ESP") (pin "J1.2") (pinfunction "LV2_J1.2") (pintype "bidirectional"))
    )
    (net (code "65") (name "Net-(LLS_ESP-LV3)") (class "Default")
      (node (ref "IO13") (pin "1") (pinfunction "1_1") (pintype "passive"))
      (node (ref "LLS_ESP") (pin "J1.5") (pinfunction "LV3_J1.5") (pintype "bidirectional"))
    )
    (net (code "66") (name "Net-(LLS_ESP-LV4)") (class "Default")
      (node (ref "IO14") (pin "1") (pinfunction "1_1") (pintype "passive"))
      (node (ref "LLS_ESP") (pin "J1.6") (pinfunction "LV4_J1.6") (pintype "bidirectional"))
    )
    (net (code "67") (name "Net-(SG1-1)") (class "Default")
      (node (ref "R3") (pin "2") (pinfunction "2_2") (pintype "passive"))
      (node (ref "SG1") (pin "-") (pinfunction "1_-") (pintype "passive"))
    )
    (net (code "68") (name "Net-(SG1-2)") (class "Default")
      (node (ref "BUZ_EN") (pin "1") (pinfunction "1_1") (pintype "passive"))
      (node (ref "SG1") (pin "+") (pinfunction "2_+") (pintype "passive"))
    )
    (net (code "69") (name "unconnected-(DHT22-N.C.-Pad3)") (class "Default")
      (node (ref "DHT22") (pin "3") (pinfunction "N.C._3") (pintype "passive"))
    )
    (net (code "70") (name "unconnected-(IC1-INTB-Pad19)") (class "Default")
      (node (ref "IC1") (pin "19") (pinfunction "INTB_19") (pintype "output"))
    )
    (net (code "71") (name "unconnected-(U$1-PadD+)") (class "Default")
      (node (ref "U$1") (pin "D+") (pinfunction "D+_D+") (pintype "bidirectional"))
    )
    (net (code "72") (name "unconnected-(U$1-PadD-)") (class "Default")
      (node (ref "U$1") (pin "D-") (pinfunction "D-_D-") (pintype "bidirectional"))
    )
  )
)
